# 18650_1S3P_Smart.net
KiCad netlist of a schematic drawn in EAGLE
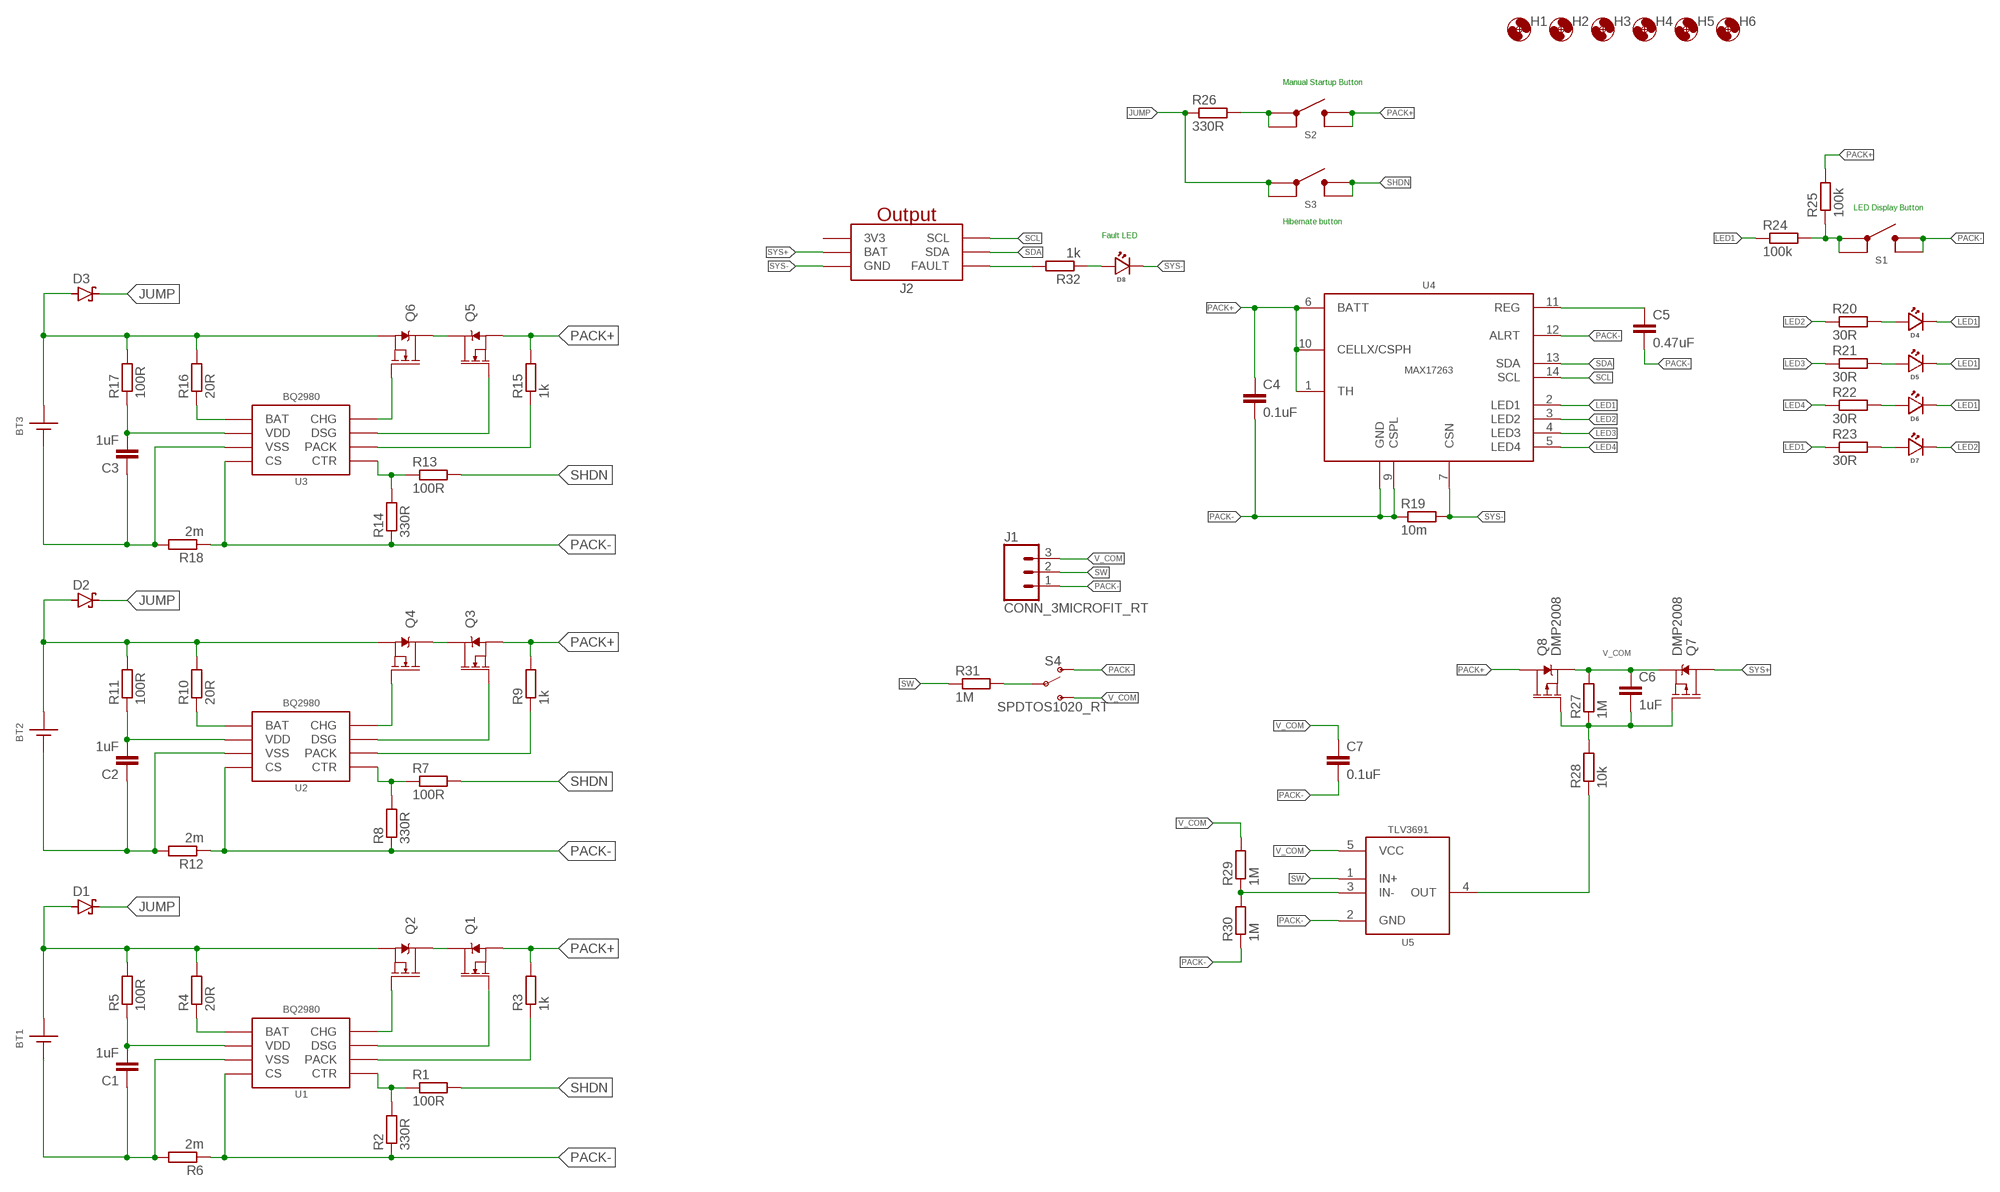
[diagram p0: schematic, sheet 1]

(export (version "E")
  (design (tool "Eeschema 10.0.6"))
  (components
    (comp (ref "BT1")
      (value "186501042P_NOSILK")
      (footprint "eagle-import:BATT_1042P_NOSILK")
      (fields (field (name "MF") "Keystone") (field (name "MPN") "1042P"))
      (libsource (lib "eagle-import") (part "186501042P_NOSILK"))
    )
    (comp (ref "BT2")
      (value "186501042P_NOSILK")
      (footprint "eagle-import:BATT_1042P_NOSILK")
      (fields (field (name "MF") "Keystone") (field (name "MPN") "1042P"))
      (libsource (lib "eagle-import") (part "186501042P_NOSILK"))
    )
    (comp (ref "BT3")
      (value "186501042P_NOSILK")
      (footprint "eagle-import:BATT_1042P_NOSILK")
      (fields (field (name "MF") "Keystone") (field (name "MPN") "1042P"))
      (libsource (lib "eagle-import") (part "186501042P_NOSILK"))
    )
    (comp (ref "C1")
      (value "1uF")
      (footprint "eagle-import:C0603")
      (fields (field (name "MF") "Yaiyo Yuden") (field (name "MPN") "EMK107BJ105KA-T"))
      (libsource (lib "eagle-import") (part "C-EUC06031UF"))
    )
    (comp (ref "C2")
      (value "1uF")
      (footprint "eagle-import:C0603")
      (fields (field (name "MF") "Yaiyo Yuden") (field (name "MPN") "EMK107BJ105KA-T"))
      (libsource (lib "eagle-import") (part "C-EUC06031UF"))
    )
    (comp (ref "C3")
      (value "1uF")
      (footprint "eagle-import:C0603")
      (fields (field (name "MF") "Yaiyo Yuden") (field (name "MPN") "EMK107BJ105KA-T"))
      (libsource (lib "eagle-import") (part "C-EUC06031UF"))
    )
    (comp (ref "C4")
      (value "0.1uF")
      (footprint "eagle-import:C0603")
      (fields (field (name "MF") "Murata") (field (name "MPN") "GCM188R71E104KA57D"))
      (libsource (lib "eagle-import") (part "C-EUC06030.1UF"))
    )
    (comp (ref "C5")
      (value "0.47uF")
      (footprint "eagle-import:C0603")
      (fields (field (name "MF") "Samsung") (field (name "MPN") "CL10B474KA8NNNC"))
      (libsource (lib "eagle-import") (part "C-EUC06030.47UF"))
    )
    (comp (ref "C6")
      (value "1uF")
      (footprint "eagle-import:C0603")
      (fields (field (name "MF") "Yaiyo Yuden") (field (name "MPN") "EMK107BJ105KA-T"))
      (libsource (lib "eagle-import") (part "C-EUC06031UF"))
    )
    (comp (ref "C7")
      (value "0.1uF")
      (footprint "eagle-import:C0603")
      (fields (field (name "MF") "Murata") (field (name "MPN") "GCM188R71E104KA57D"))
      (libsource (lib "eagle-import") (part "C-EUC06030.1UF"))
    )
    (comp (ref "D1")
      (value "DIODE_SCHOTTKYSOD-323")
      (footprint "eagle-import:SOD323-R")
      (fields
        (field (name "DIGIKEY") "BAT54WS-FDICT-ND")
        (field (name "MF") "Diodes Inc")
        (field (name "MPN") "BAT54WS-7-F")
      )
      (libsource (lib "eagle-import") (part "DIODE_SCHOTTKYSOD-323"))
    )
    (comp (ref "D2")
      (value "DIODE_SCHOTTKYSOD-323")
      (footprint "eagle-import:SOD323-R")
      (fields
        (field (name "DIGIKEY") "BAT54WS-FDICT-ND")
        (field (name "MF") "Diodes Inc")
        (field (name "MPN") "BAT54WS-7-F")
      )
      (libsource (lib "eagle-import") (part "DIODE_SCHOTTKYSOD-323"))
    )
    (comp (ref "D3")
      (value "DIODE_SCHOTTKYSOD-323")
      (footprint "eagle-import:SOD323-R")
      (fields
        (field (name "DIGIKEY") "BAT54WS-FDICT-ND")
        (field (name "MF") "Diodes Inc")
        (field (name "MPN") "BAT54WS-7-F")
      )
      (libsource (lib "eagle-import") (part "DIODE_SCHOTTKYSOD-323"))
    )
    (comp (ref "D4")
      (value "LED1206_BOTTOM")
      (footprint "eagle-import:LED_1206_BOTTOM")
      (fields (field (name "MF") "Lite-On") (field (name "MPN") "LTST-C230KGKT"))
      (libsource (lib "eagle-import") (part "LED1206_BOTTOM"))
    )
    (comp (ref "D5")
      (value "LED1206_BOTTOM")
      (footprint "eagle-import:LED_1206_BOTTOM")
      (fields (field (name "MF") "Lite-On") (field (name "MPN") "LTST-C230KGKT"))
      (libsource (lib "eagle-import") (part "LED1206_BOTTOM"))
    )
    (comp (ref "D6")
      (value "LED1206_BOTTOM")
      (footprint "eagle-import:LED_1206_BOTTOM")
      (fields (field (name "MF") "Lite-On") (field (name "MPN") "LTST-C230KGKT"))
      (libsource (lib "eagle-import") (part "LED1206_BOTTOM"))
    )
    (comp (ref "D7")
      (value "LED1206_BOTTOM")
      (footprint "eagle-import:LED_1206_BOTTOM")
      (fields (field (name "MF") "Lite-On") (field (name "MPN") "LTST-C230KGKT"))
      (libsource (lib "eagle-import") (part "LED1206_BOTTOM"))
    )
    (comp (ref "D8")
      (value "LED1206_BOTTOM")
      (footprint "eagle-import:LED_1206_BOTTOM")
      (fields (field (name "MF") "Lite-On") (field (name "MPN") "LTST-C230KRKT"))
      (libsource (lib "eagle-import") (part "LED1206_BOTTOM"))
    )
    (comp (ref "H1")
      (value "MOUNTING_HOLE4_NP")
      (footprint "eagle-import:4_40")
      (fields (field (name "MPN") "DNP"))
      (libsource (lib "eagle-import") (part "MOUNTING_HOLE4_NP"))
    )
    (comp (ref "H2")
      (value "MOUNTING_HOLE4_NP")
      (footprint "eagle-import:4_40")
      (fields (field (name "MPN") "DNP"))
      (libsource (lib "eagle-import") (part "MOUNTING_HOLE4_NP"))
    )
    (comp (ref "H3")
      (value "MOUNTING_HOLE4_NP")
      (footprint "eagle-import:4_40")
      (fields (field (name "MPN") "DNP"))
      (libsource (lib "eagle-import") (part "MOUNTING_HOLE4_NP"))
    )
    (comp (ref "H4")
      (value "MOUNTING_HOLE4_NP")
      (footprint "eagle-import:4_40")
      (fields (field (name "MPN") "DNP"))
      (libsource (lib "eagle-import") (part "MOUNTING_HOLE4_NP"))
    )
    (comp (ref "H5")
      (value "MOUNTING_HOLE4_NP")
      (footprint "eagle-import:4_40")
      (fields (field (name "MPN") "DNP"))
      (libsource (lib "eagle-import") (part "MOUNTING_HOLE4_NP"))
    )
    (comp (ref "H6")
      (value "MOUNTING_HOLE4_NP")
      (footprint "eagle-import:4_40")
      (fields (field (name "MPN") "DNP"))
      (libsource (lib "eagle-import") (part "MOUNTING_HOLE4_NP"))
    )
    (comp (ref "J1")
      (value "CONN_3MICROFIT_RT")
      (footprint "eagle-import:1X3_MICROFIT_RT")
      (fields (field (name "MF") "Molex") (field (name "MPN") "0436500300"))
      (libsource (lib "eagle-import") (part "CONN_3MICROFIT_RT"))
    )
    (comp (ref "J2")
      (value "GEMS_POWER_PLUGOUTPUT")
      (footprint "eagle-import:2X3_MICROFIT_RT")
      (fields (field (name "DISP") "Output") (field (name "MF") "Molex") (field (name "MPN") "0430450600"))
      (libsource (lib "eagle-import") (part "GEMS_POWER_PLUGOUTPUT"))
    )
    (comp (ref "Q1")
      (value "AON7522E")
      (footprint "eagle-import:DFN3X3A_8L_EP1_P")
      (fields (field (name "MF") "Alpha & Omega"))
      (libsource (lib "eagle-import") (part "MOSFET-NCH-AON7522E"))
    )
    (comp (ref "Q2")
      (value "AON7522E")
      (footprint "eagle-import:DFN3X3A_8L_EP1_P")
      (fields (field (name "MF") "Alpha & Omega"))
      (libsource (lib "eagle-import") (part "MOSFET-NCH-AON7522E"))
    )
    (comp (ref "Q3")
      (value "AON7522E")
      (footprint "eagle-import:DFN3X3A_8L_EP1_P")
      (fields (field (name "MF") "Alpha & Omega"))
      (libsource (lib "eagle-import") (part "MOSFET-NCH-AON7522E"))
    )
    (comp (ref "Q4")
      (value "AON7522E")
      (footprint "eagle-import:DFN3X3A_8L_EP1_P")
      (fields (field (name "MF") "Alpha & Omega"))
      (libsource (lib "eagle-import") (part "MOSFET-NCH-AON7522E"))
    )
    (comp (ref "Q5")
      (value "AON7522E")
      (footprint "eagle-import:DFN3X3A_8L_EP1_P")
      (fields (field (name "MF") "Alpha & Omega"))
      (libsource (lib "eagle-import") (part "MOSFET-NCH-AON7522E"))
    )
    (comp (ref "Q6")
      (value "AON7522E")
      (footprint "eagle-import:DFN3X3A_8L_EP1_P")
      (fields (field (name "MF") "Alpha & Omega"))
      (libsource (lib "eagle-import") (part "MOSFET-NCH-AON7522E"))
    )
    (comp (ref "Q7")
      (value "DMP2008")
      (footprint "eagle-import:POWERDI3333-8")
      (fields (field (name "MF") "Diodes Inc") (field (name "MPN") "DMP2008UFG-7"))
      (libsource (lib "eagle-import") (part "MOSFET-PCH-DMP2008"))
    )
    (comp (ref "Q8")
      (value "DMP2008")
      (footprint "eagle-import:POWERDI3333-8")
      (fields (field (name "MF") "Diodes Inc") (field (name "MPN") "DMP2008UFG-7"))
      (libsource (lib "eagle-import") (part "MOSFET-PCH-DMP2008"))
    )
    (comp (ref "R1")
      (value "100R")
      (footprint "eagle-import:R0603")
      (fields
        (field (name "MF") "Yageo")
        (field (name "MPN") "RC0603FR-07100RL")
        (field (name "VALUE_PART") "100")
      )
      (libsource (lib "eagle-import") (part "R-EU_R0603100"))
    )
    (comp (ref "R2")
      (value "330R")
      (footprint "eagle-import:R0603")
      (fields
        (field (name "MF") "Yageo")
        (field (name "MPN") "RC0603FR-07330RL")
        (field (name "VALUE_PART") "330")
      )
      (libsource (lib "eagle-import") (part "R-EU_R0603330"))
    )
    (comp (ref "R3")
      (value "1k")
      (footprint "eagle-import:R0603")
      (fields (field (name "MF") "Yageo") (field (name "MPN") "AC0603FR-071KL"))
      (libsource (lib "eagle-import") (part "R-EU_R06031K"))
    )
    (comp (ref "R4")
      (value "20R")
      (footprint "eagle-import:R0603")
      (fields
        (field (name "MF") "Yageo")
        (field (name "MPN") "RC0603FR-0720RL")
        (field (name "VALUE_PART") "20")
      )
      (libsource (lib "eagle-import") (part "R-EU_R060320"))
    )
    (comp (ref "R5")
      (value "100R")
      (footprint "eagle-import:R0603")
      (fields
        (field (name "MF") "Yageo")
        (field (name "MPN") "RC0603FR-07100RL")
        (field (name "VALUE_PART") "100")
      )
      (libsource (lib "eagle-import") (part "R-EU_R0603100"))
    )
    (comp (ref "R6")
      (value "2m")
      (footprint "eagle-import:R0805")
      (fields (field (name "MF") "Rohm") (field (name "MPN") "PMR10EZPFV2L00"))
      (libsource (lib "eagle-import") (part "R-EU_R08050.002"))
    )
    (comp (ref "R7")
      (value "100R")
      (footprint "eagle-import:R0603")
      (fields
        (field (name "MF") "Yageo")
        (field (name "MPN") "RC0603FR-07100RL")
        (field (name "VALUE_PART") "100")
      )
      (libsource (lib "eagle-import") (part "R-EU_R0603100"))
    )
    (comp (ref "R8")
      (value "330R")
      (footprint "eagle-import:R0603")
      (fields
        (field (name "MF") "Yageo")
        (field (name "MPN") "RC0603FR-07330RL")
        (field (name "VALUE_PART") "330")
      )
      (libsource (lib "eagle-import") (part "R-EU_R0603330"))
    )
    (comp (ref "R9")
      (value "1k")
      (footprint "eagle-import:R0603")
      (fields (field (name "MF") "Yageo") (field (name "MPN") "AC0603FR-071KL"))
      (libsource (lib "eagle-import") (part "R-EU_R06031K"))
    )
    (comp (ref "R10")
      (value "20R")
      (footprint "eagle-import:R0603")
      (fields
        (field (name "MF") "Yageo")
        (field (name "MPN") "RC0603FR-0720RL")
        (field (name "VALUE_PART") "20")
      )
      (libsource (lib "eagle-import") (part "R-EU_R060320"))
    )
    (comp (ref "R11")
      (value "100R")
      (footprint "eagle-import:R0603")
      (fields
        (field (name "MF") "Yageo")
        (field (name "MPN") "RC0603FR-07100RL")
        (field (name "VALUE_PART") "100")
      )
      (libsource (lib "eagle-import") (part "R-EU_R0603100"))
    )
    (comp (ref "R12")
      (value "2m")
      (footprint "eagle-import:R0805")
      (fields (field (name "MF") "Rohm") (field (name "MPN") "PMR10EZPFV2L00"))
      (libsource (lib "eagle-import") (part "R-EU_R08050.002"))
    )
    (comp (ref "R13")
      (value "100R")
      (footprint "eagle-import:R0603")
      (fields
        (field (name "MF") "Yageo")
        (field (name "MPN") "RC0603FR-07100RL")
        (field (name "VALUE_PART") "100")
      )
      (libsource (lib "eagle-import") (part "R-EU_R0603100"))
    )
    (comp (ref "R14")
      (value "330R")
      (footprint "eagle-import:R0603")
      (fields
        (field (name "MF") "Yageo")
        (field (name "MPN") "RC0603FR-07330RL")
        (field (name "VALUE_PART") "330")
      )
      (libsource (lib "eagle-import") (part "R-EU_R0603330"))
    )
    (comp (ref "R15")
      (value "1k")
      (footprint "eagle-import:R0603")
      (fields (field (name "MF") "Yageo") (field (name "MPN") "AC0603FR-071KL"))
      (libsource (lib "eagle-import") (part "R-EU_R06031K"))
    )
    (comp (ref "R16")
      (value "20R")
      (footprint "eagle-import:R0603")
      (fields
        (field (name "MF") "Yageo")
        (field (name "MPN") "RC0603FR-0720RL")
        (field (name "VALUE_PART") "20")
      )
      (libsource (lib "eagle-import") (part "R-EU_R060320"))
    )
    (comp (ref "R17")
      (value "100R")
      (footprint "eagle-import:R0603")
      (fields
        (field (name "MF") "Yageo")
        (field (name "MPN") "RC0603FR-07100RL")
        (field (name "VALUE_PART") "100")
      )
      (libsource (lib "eagle-import") (part "R-EU_R0603100"))
    )
    (comp (ref "R18")
      (value "2m")
      (footprint "eagle-import:R0805")
      (fields (field (name "MF") "Rohm") (field (name "MPN") "PMR10EZPFV2L00"))
      (libsource (lib "eagle-import") (part "R-EU_R08050.002"))
    )
    (comp (ref "R19")
      (value "10m")
      (footprint "eagle-import:R0805")
      (fields (field (name "MF") "Bourns") (field (name "MPN") "CRF0805-FZ-R010ELF"))
      (libsource (lib "eagle-import") (part "R-EU_R08050.01"))
    )
    (comp (ref "R20")
      (value "30R")
      (footprint "eagle-import:R0603")
      (fields
        (field (name "MF") "Yageo")
        (field (name "MPN") "RC0603FR-0730RL")
        (field (name "VALUE_PART") "30")
      )
      (libsource (lib "eagle-import") (part "R-EU_R060330"))
    )
    (comp (ref "R21")
      (value "30R")
      (footprint "eagle-import:R0603")
      (fields
        (field (name "MF") "Yageo")
        (field (name "MPN") "RC0603FR-0730RL")
        (field (name "VALUE_PART") "30")
      )
      (libsource (lib "eagle-import") (part "R-EU_R060330"))
    )
    (comp (ref "R22")
      (value "30R")
      (footprint "eagle-import:R0603")
      (fields
        (field (name "MF") "Yageo")
        (field (name "MPN") "RC0603FR-0730RL")
        (field (name "VALUE_PART") "30")
      )
      (libsource (lib "eagle-import") (part "R-EU_R060330"))
    )
    (comp (ref "R23")
      (value "30R")
      (footprint "eagle-import:R0603")
      (fields
        (field (name "MF") "Yageo")
        (field (name "MPN") "RC0603FR-0730RL")
        (field (name "VALUE_PART") "30")
      )
      (libsource (lib "eagle-import") (part "R-EU_R060330"))
    )
    (comp (ref "R24")
      (value "100k")
      (footprint "eagle-import:R0603")
      (fields (field (name "MF") "Yageo") (field (name "MPN") "RC0603FR-07100KL"))
      (libsource (lib "eagle-import") (part "R-EU_R0603100K"))
    )
    (comp (ref "R25")
      (value "100k")
      (footprint "eagle-import:R0603")
      (fields (field (name "MF") "Yageo") (field (name "MPN") "RC0603FR-07100KL"))
      (libsource (lib "eagle-import") (part "R-EU_R0603100K"))
    )
    (comp (ref "R26")
      (value "330R")
      (footprint "eagle-import:R0603")
      (fields
        (field (name "MF") "Yageo")
        (field (name "MPN") "RC0603FR-07330RL")
        (field (name "VALUE_PART") "330")
      )
      (libsource (lib "eagle-import") (part "R-EU_R0603330"))
    )
    (comp (ref "R27")
      (value "1M")
      (footprint "eagle-import:R0603")
      (fields (field (name "MF") "Panasonic") (field (name "MPN") "ERJ-3EKF1004V"))
      (libsource (lib "eagle-import") (part "R-EU_R06031M"))
    )
    (comp (ref "R28")
      (value "10k")
      (footprint "eagle-import:R0603")
      (fields (field (name "MF") "Yageo") (field (name "MPN") "RC0603FR-0710KL"))
      (libsource (lib "eagle-import") (part "R-EU_R060310K"))
    )
    (comp (ref "R29")
      (value "1M")
      (footprint "eagle-import:R0603")
      (fields (field (name "MF") "Panasonic") (field (name "MPN") "ERJ-3EKF1004V"))
      (libsource (lib "eagle-import") (part "R-EU_R06031M"))
    )
    (comp (ref "R30")
      (value "1M")
      (footprint "eagle-import:R0603")
      (fields (field (name "MF") "Panasonic") (field (name "MPN") "ERJ-3EKF1004V"))
      (libsource (lib "eagle-import") (part "R-EU_R06031M"))
    )
    (comp (ref "R31")
      (value "1M")
      (footprint "eagle-import:R0603")
      (fields (field (name "MF") "Panasonic") (field (name "MPN") "ERJ-3EKF1004V"))
      (libsource (lib "eagle-import") (part "R-EU_R06031M"))
    )
    (comp (ref "R32")
      (value "1k")
      (footprint "eagle-import:R0603")
      (fields (field (name "MF") "Yageo") (field (name "MPN") "AC0603FR-071KL"))
      (libsource (lib "eagle-import") (part "R-EU_R06031K"))
    )
    (comp (ref "S1")
      (value "BUTTON6X6_TH")
      (footprint "eagle-import:SWITCH_6MM_TH")
      (fields (field (name "MF") "TE Connectivity") (field (name "MPN") "1825910-6"))
      (libsource (lib "eagle-import") (part "BUTTON6X6_TH"))
    )
    (comp (ref "S2")
      (value "BUTTON6X6_TH")
      (footprint "eagle-import:SWITCH_6MM_TH")
      (fields (field (name "MF") "TE Connectivity") (field (name "MPN") "1825910-6"))
      (libsource (lib "eagle-import") (part "BUTTON6X6_TH"))
    )
    (comp (ref "S3")
      (value "BUTTON6X6_TH")
      (footprint "eagle-import:SWITCH_6MM_TH")
      (fields (field (name "MF") "TE Connectivity") (field (name "MPN") "1825910-6"))
      (libsource (lib "eagle-import") (part "BUTTON6X6_TH"))
    )
    (comp (ref "S4")
      (value "SPDTOS1020_RT")
      (footprint "eagle-import:OS102011MA1QN1")
      (fields (field (name "MF") "C&K") (field (name "MPN") "OS102011MA1QN1"))
      (libsource (lib "eagle-import") (part "SPDTOS1020_RT"))
    )
    (comp (ref "U1")
      (value "BQ2980RUG")
      (footprint "eagle-import:RUG_S-PQFP-N8")
      (fields (field (name "MF") "TI") (field (name "MPN") "BQ298000RUGT"))
      (libsource (lib "eagle-import") (part "BQ2980RUG"))
    )
    (comp (ref "U2")
      (value "BQ2980RUG")
      (footprint "eagle-import:RUG_S-PQFP-N8")
      (fields (field (name "MF") "TI") (field (name "MPN") "BQ298000RUGT"))
      (libsource (lib "eagle-import") (part "BQ2980RUG"))
    )
    (comp (ref "U3")
      (value "BQ2980RUG")
      (footprint "eagle-import:RUG_S-PQFP-N8")
      (fields (field (name "MF") "TI") (field (name "MPN") "BQ298000RUGT"))
      (libsource (lib "eagle-import") (part "BQ2980RUG"))
    )
    (comp (ref "U4")
      (value "MAX17263")
      (footprint "eagle-import:DFN_14_3X3")
      (fields (field (name "MF") "Maxim") (field (name "MPN") "MAX17263LETD+T"))
      (libsource (lib "eagle-import") (part "MAX17263"))
    )
    (comp (ref "U5")
      (value "TLV3691DCK")
      (footprint "eagle-import:DCK_R-PDSO-G5")
      (fields (field (name "MF") "TI") (field (name "MPN") "TLV3691IDCKR"))
      (libsource (lib "eagle-import") (part "TLV3691DCK"))
    )
  )
  (nets
    (net (code "1") (name "/3V3") (class "Default")
      (node (ref "J2") (pin "5") (pinfunction "3V3_5") (pintype "power_in"))
    )
    (net (code "2") (name "JUMP") (class "Default")
      (node (ref "D1") (pin "C") (pinfunction "C_C") (pintype "passive"))
      (node (ref "D2") (pin "C") (pinfunction "C_C") (pintype "passive"))
      (node (ref "D3") (pin "C") (pinfunction "C_C") (pintype "passive"))
      (node (ref "R26") (pin "1") (pinfunction "1_1") (pintype "passive"))
      (node (ref "S3") (pin "1") (pinfunction "1_1") (pintype "bidirectional"))
      (node (ref "S3") (pin "2") (pinfunction "2_2") (pintype "bidirectional"))
    )
    (net (code "3") (name "LED1") (class "Default")
      (node (ref "D4") (pin "CATHODE") (pinfunction "CATHODE_CATHODE") (pintype "power_in"))
      (node (ref "D5") (pin "CATHODE") (pinfunction "CATHODE_CATHODE") (pintype "power_in"))
      (node (ref "D6") (pin "CATHODE") (pinfunction "CATHODE_CATHODE") (pintype "power_in"))
      (node (ref "R23") (pin "1") (pinfunction "1_1") (pintype "passive"))
      (node (ref "R24") (pin "1") (pinfunction "1_1") (pintype "passive"))
      (node (ref "U4") (pin "2") (pinfunction "LED1_2") (pintype "bidirectional"))
    )
    (net (code "4") (name "LED2") (class "Default")
      (node (ref "D7") (pin "CATHODE") (pinfunction "CATHODE_CATHODE") (pintype "power_in"))
      (node (ref "R20") (pin "1") (pinfunction "1_1") (pintype "passive"))
      (node (ref "U4") (pin "3") (pinfunction "LED2_3") (pintype "bidirectional"))
    )
    (net (code "5") (name "LED3") (class "Default")
      (node (ref "R21") (pin "1") (pinfunction "1_1") (pintype "passive"))
      (node (ref "U4") (pin "4") (pinfunction "LED3_4") (pintype "bidirectional"))
    )
    (net (code "6") (name "LED4") (class "Default")
      (node (ref "R22") (pin "1") (pinfunction "1_1") (pintype "passive"))
      (node (ref "U4") (pin "5") (pinfunction "LED4_5") (pintype "bidirectional"))
    )
    (net (code "7") (name "Net-(BT1-+)") (class "Default")
      (node (ref "BT1") (pin "BATT+") (pinfunction "+_BATT+") (pintype "power_in"))
      (node (ref "D1") (pin "A") (pinfunction "A_A") (pintype "passive"))
      (node (ref "Q2") (pin "S@1") (pinfunction "S_S@1") (pintype "bidirectional"))
      (node (ref "Q2") (pin "S@2") (pinfunction "S_S@2") (pintype "bidirectional"))
      (node (ref "Q2") (pin "S@3") (pinfunction "S_S@3") (pintype "bidirectional"))
      (node (ref "R4") (pin "2") (pinfunction "2_2") (pintype "passive"))
      (node (ref "R5") (pin "2") (pinfunction "2_2") (pintype "passive"))
    )
    (net (code "8") (name "Net-(BT1--)") (class "Default")
      (node (ref "BT1") (pin "BATT-") (pinfunction "-_BATT-") (pintype "power_in"))
      (node (ref "C1") (pin "1") (pinfunction "1_1") (pintype "passive"))
      (node (ref "R6") (pin "2") (pinfunction "2_2") (pintype "passive"))
      (node (ref "U1") (pin "3") (pinfunction "VSS_3") (pintype "power_in"))
    )
    (net (code "9") (name "Net-(BT2-+)") (class "Default")
      (node (ref "BT2") (pin "BATT+") (pinfunction "+_BATT+") (pintype "power_in"))
      (node (ref "D2") (pin "A") (pinfunction "A_A") (pintype "passive"))
      (node (ref "Q4") (pin "S@1") (pinfunction "S_S@1") (pintype "bidirectional"))
      (node (ref "Q4") (pin "S@2") (pinfunction "S_S@2") (pintype "bidirectional"))
      (node (ref "Q4") (pin "S@3") (pinfunction "S_S@3") (pintype "bidirectional"))
      (node (ref "R10") (pin "2") (pinfunction "2_2") (pintype "passive"))
      (node (ref "R11") (pin "2") (pinfunction "2_2") (pintype "passive"))
    )
    (net (code "10") (name "Net-(BT2--)") (class "Default")
      (node (ref "BT2") (pin "BATT-") (pinfunction "-_BATT-") (pintype "power_in"))
      (node (ref "C2") (pin "1") (pinfunction "1_1") (pintype "passive"))
      (node (ref "R12") (pin "2") (pinfunction "2_2") (pintype "passive"))
      (node (ref "U2") (pin "3") (pinfunction "VSS_3") (pintype "power_in"))
    )
    (net (code "11") (name "Net-(BT3-+)") (class "Default")
      (node (ref "BT3") (pin "BATT+") (pinfunction "+_BATT+") (pintype "power_in"))
      (node (ref "D3") (pin "A") (pinfunction "A_A") (pintype "passive"))
      (node (ref "Q6") (pin "S@1") (pinfunction "S_S@1") (pintype "bidirectional"))
      (node (ref "Q6") (pin "S@2") (pinfunction "S_S@2") (pintype "bidirectional"))
      (node (ref "Q6") (pin "S@3") (pinfunction "S_S@3") (pintype "bidirectional"))
      (node (ref "R16") (pin "2") (pinfunction "2_2") (pintype "passive"))
      (node (ref "R17") (pin "2") (pinfunction "2_2") (pintype "passive"))
    )
    (net (code "12") (name "Net-(BT3--)") (class "Default")
      (node (ref "BT3") (pin "BATT-") (pinfunction "-_BATT-") (pintype "power_in"))
      (node (ref "C3") (pin "1") (pinfunction "1_1") (pintype "passive"))
      (node (ref "R18") (pin "2") (pinfunction "2_2") (pintype "passive"))
      (node (ref "U3") (pin "3") (pinfunction "VSS_3") (pintype "power_in"))
    )
    (net (code "13") (name "Net-(D4-PadANODE)") (class "Default")
      (node (ref "D4") (pin "ANODE") (pinfunction "ANODE_ANODE") (pintype "power_in"))
      (node (ref "R20") (pin "2") (pinfunction "2_2") (pintype "passive"))
    )
    (net (code "14") (name "Net-(D5-PadANODE)") (class "Default")
      (node (ref "D5") (pin "ANODE") (pinfunction "ANODE_ANODE") (pintype "power_in"))
      (node (ref "R21") (pin "2") (pinfunction "2_2") (pintype "passive"))
    )
    (net (code "15") (name "Net-(D6-PadANODE)") (class "Default")
      (node (ref "D6") (pin "ANODE") (pinfunction "ANODE_ANODE") (pintype "power_in"))
      (node (ref "R22") (pin "2") (pinfunction "2_2") (pintype "passive"))
    )
    (net (code "16") (name "Net-(D7-PadANODE)") (class "Default")
      (node (ref "D7") (pin "ANODE") (pinfunction "ANODE_ANODE") (pintype "power_in"))
      (node (ref "R23") (pin "2") (pinfunction "2_2") (pintype "passive"))
    )
    (net (code "17") (name "Net-(D8-PadANODE)") (class "Default")
      (node (ref "D8") (pin "ANODE") (pinfunction "ANODE_ANODE") (pintype "power_in"))
      (node (ref "R32") (pin "1") (pinfunction "1_1") (pintype "passive"))
    )
    (net (code "18") (name "Net-(J2-FAULT)") (class "Default")
      (node (ref "J2") (pin "1") (pinfunction "FAULT_1") (pintype "bidirectional"))
      (node (ref "R32") (pin "2") (pinfunction "2_2") (pintype "passive"))
    )
    (net (code "19") (name "Net-(Q1-PadD)") (class "Default")
      (node (ref "Q1") (pin "D") (pinfunction "D_D") (pintype "bidirectional"))
      (node (ref "Q2") (pin "D") (pinfunction "D_D") (pintype "bidirectional"))
    )
    (net (code "20") (name "Net-(Q3-PadD)") (class "Default")
      (node (ref "Q3") (pin "D") (pinfunction "D_D") (pintype "bidirectional"))
      (node (ref "Q4") (pin "D") (pinfunction "D_D") (pintype "bidirectional"))
    )
    (net (code "21") (name "Net-(Q5-PadD)") (class "Default")
      (node (ref "Q5") (pin "D") (pinfunction "D_D") (pintype "bidirectional"))
      (node (ref "Q6") (pin "D") (pinfunction "D_D") (pintype "bidirectional"))
    )
    (net (code "22") (name "Net-(Q7-G)") (class "Default")
      (node (ref "C6") (pin "2") (pinfunction "2_2") (pintype "passive"))
      (node (ref "Q7") (pin "4") (pinfunction "G_4") (pintype "bidirectional"))
      (node (ref "Q8") (pin "4") (pinfunction "G_4") (pintype "bidirectional"))
      (node (ref "R27") (pin "1") (pinfunction "1_1") (pintype "passive"))
      (node (ref "R28") (pin "2") (pinfunction "2_2") (pintype "passive"))
    )
    (net (code "23") (name "Net-(R24-Pad2)") (class "Default")
      (node (ref "R24") (pin "2") (pinfunction "2_2") (pintype "passive"))
      (node (ref "R25") (pin "1") (pinfunction "1_1") (pintype "passive"))
      (node (ref "S1") (pin "1") (pinfunction "1_1") (pintype "bidirectional"))
      (node (ref "S1") (pin "2") (pinfunction "2_2") (pintype "bidirectional"))
    )
    (net (code "24") (name "Net-(R26-Pad2)") (class "Default")
      (node (ref "R26") (pin "2") (pinfunction "2_2") (pintype "passive"))
      (node (ref "S2") (pin "1") (pinfunction "1_1") (pintype "bidirectional"))
      (node (ref "S2") (pin "2") (pinfunction "2_2") (pintype "bidirectional"))
    )
    (net (code "25") (name "Net-(S4-P)") (class "Default")
      (node (ref "R31") (pin "2") (pinfunction "2_2") (pintype "passive"))
      (node (ref "S4") (pin "2") (pinfunction "P_2") (pintype "passive"))
    )
    (net (code "26") (name "Net-(U1-BAT)") (class "Default")
      (node (ref "R4") (pin "1") (pinfunction "1_1") (pintype "passive"))
      (node (ref "U1") (pin "1") (pinfunction "BAT_1") (pintype "power_in"))
    )
    (net (code "27") (name "Net-(U1-CHG)") (class "Default")
      (node (ref "Q2") (pin "G") (pinfunction "G_G") (pintype "bidirectional"))
      (node (ref "U1") (pin "8") (pinfunction "CHG_8") (pintype "output"))
    )
    (net (code "28") (name "Net-(U1-CTR)") (class "Default")
      (node (ref "R1") (pin "1") (pinfunction "1_1") (pintype "passive"))
      (node (ref "R2") (pin "2") (pinfunction "2_2") (pintype "passive"))
      (node (ref "U1") (pin "5") (pinfunction "CTR_5") (pintype "input"))
    )
    (net (code "29") (name "Net-(U1-DSG)") (class "Default")
      (node (ref "Q1") (pin "G") (pinfunction "G_G") (pintype "bidirectional"))
      (node (ref "U1") (pin "7") (pinfunction "DSG_7") (pintype "output"))
    )
    (net (code "30") (name "Net-(U1-PACK)") (class "Default")
      (node (ref "R3") (pin "1") (pinfunction "1_1") (pintype "passive"))
      (node (ref "U1") (pin "6") (pinfunction "PACK_6") (pintype "input"))
    )
    (net (code "31") (name "Net-(U1-VDD)") (class "Default")
      (node (ref "C1") (pin "2") (pinfunction "2_2") (pintype "passive"))
      (node (ref "R5") (pin "1") (pinfunction "1_1") (pintype "passive"))
      (node (ref "U1") (pin "2") (pinfunction "VDD_2") (pintype "power_in"))
    )
    (net (code "32") (name "Net-(U2-BAT)") (class "Default")
      (node (ref "R10") (pin "1") (pinfunction "1_1") (pintype "passive"))
      (node (ref "U2") (pin "1") (pinfunction "BAT_1") (pintype "power_in"))
    )
    (net (code "33") (name "Net-(U2-CHG)") (class "Default")
      (node (ref "Q4") (pin "G") (pinfunction "G_G") (pintype "bidirectional"))
      (node (ref "U2") (pin "8") (pinfunction "CHG_8") (pintype "output"))
    )
    (net (code "34") (name "Net-(U2-CTR)") (class "Default")
      (node (ref "R7") (pin "1") (pinfunction "1_1") (pintype "passive"))
      (node (ref "R8") (pin "2") (pinfunction "2_2") (pintype "passive"))
      (node (ref "U2") (pin "5") (pinfunction "CTR_5") (pintype "input"))
    )
    (net (code "35") (name "Net-(U2-DSG)") (class "Default")
      (node (ref "Q3") (pin "G") (pinfunction "G_G") (pintype "bidirectional"))
      (node (ref "U2") (pin "7") (pinfunction "DSG_7") (pintype "output"))
    )
    (net (code "36") (name "Net-(U2-PACK)") (class "Default")
      (node (ref "R9") (pin "1") (pinfunction "1_1") (pintype "passive"))
      (node (ref "U2") (pin "6") (pinfunction "PACK_6") (pintype "input"))
    )
    (net (code "37") (name "Net-(U2-VDD)") (class "Default")
      (node (ref "C2") (pin "2") (pinfunction "2_2") (pintype "passive"))
      (node (ref "R11") (pin "1") (pinfunction "1_1") (pintype "passive"))
      (node (ref "U2") (pin "2") (pinfunction "VDD_2") (pintype "power_in"))
    )
    (net (code "38") (name "Net-(U3-BAT)") (class "Default")
      (node (ref "R16") (pin "1") (pinfunction "1_1") (pintype "passive"))
      (node (ref "U3") (pin "1") (pinfunction "BAT_1") (pintype "power_in"))
    )
    (net (code "39") (name "Net-(U3-CHG)") (class "Default")
      (node (ref "Q6") (pin "G") (pinfunction "G_G") (pintype "bidirectional"))
      (node (ref "U3") (pin "8") (pinfunction "CHG_8") (pintype "output"))
    )
    (net (code "40") (name "Net-(U3-CTR)") (class "Default")
      (node (ref "R13") (pin "1") (pinfunction "1_1") (pintype "passive"))
      (node (ref "R14") (pin "2") (pinfunction "2_2") (pintype "passive"))
      (node (ref "U3") (pin "5") (pinfunction "CTR_5") (pintype "input"))
    )
    (net (code "41") (name "Net-(U3-DSG)") (class "Default")
      (node (ref "Q5") (pin "G") (pinfunction "G_G") (pintype "bidirectional"))
      (node (ref "U3") (pin "7") (pinfunction "DSG_7") (pintype "output"))
    )
    (net (code "42") (name "Net-(U3-PACK)") (class "Default")
      (node (ref "R15") (pin "1") (pinfunction "1_1") (pintype "passive"))
      (node (ref "U3") (pin "6") (pinfunction "PACK_6") (pintype "input"))
    )
    (net (code "43") (name "Net-(U3-VDD)") (class "Default")
      (node (ref "C3") (pin "2") (pinfunction "2_2") (pintype "passive"))
      (node (ref "R17") (pin "1") (pinfunction "1_1") (pintype "passive"))
      (node (ref "U3") (pin "2") (pinfunction "VDD_2") (pintype "power_in"))
    )
    (net (code "44") (name "Net-(U4-REG)") (class "Default")
      (node (ref "C5") (pin "1") (pinfunction "1_1") (pintype "passive"))
      (node (ref "U4") (pin "11") (pinfunction "REG_11") (pintype "power_in"))
    )
    (net (code "45") (name "Net-(U5-IN-)") (class "Default")
      (node (ref "R29") (pin "1") (pinfunction "1_1") (pintype "passive"))
      (node (ref "R30") (pin "2") (pinfunction "2_2") (pintype "passive"))
      (node (ref "U5") (pin "3") (pinfunction "IN-_3") (pintype "input"))
    )
    (net (code "46") (name "Net-(U5-OUT)") (class "Default")
      (node (ref "R28") (pin "1") (pinfunction "1_1") (pintype "passive"))
      (node (ref "U5") (pin "4") (pinfunction "OUT_4") (pintype "output"))
    )
    (net (code "47") (name "PACK+") (class "Default")
      (node (ref "C4") (pin "1") (pinfunction "1_1") (pintype "passive"))
      (node (ref "Q1") (pin "S@1") (pinfunction "S_S@1") (pintype "bidirectional"))
      (node (ref "Q1") (pin "S@2") (pinfunction "S_S@2") (pintype "bidirectional"))
      (node (ref "Q1") (pin "S@3") (pinfunction "S_S@3") (pintype "bidirectional"))
      (node (ref "Q3") (pin "S@1") (pinfunction "S_S@1") (pintype "bidirectional"))
      (node (ref "Q3") (pin "S@2") (pinfunction "S_S@2") (pintype "bidirectional"))
      (node (ref "Q3") (pin "S@3") (pinfunction "S_S@3") (pintype "bidirectional"))
      (node (ref "Q5") (pin "S@1") (pinfunction "S_S@1") (pintype "bidirectional"))
      (node (ref "Q5") (pin "S@2") (pinfunction "S_S@2") (pintype "bidirectional"))
      (node (ref "Q5") (pin "S@3") (pinfunction "S_S@3") (pintype "bidirectional"))
      (node (ref "Q8") (pin "EP@1") (pinfunction "D_EP@1") (pintype "bidirectional"))
      (node (ref "Q8") (pin "EP@2") (pinfunction "D_EP@2") (pintype "bidirectional"))
      (node (ref "Q8") (pin "EP@3") (pinfunction "D_EP@3") (pintype "bidirectional"))
      (node (ref "Q8") (pin "EP@4") (pinfunction "D_EP@4") (pintype "bidirectional"))
      (node (ref "Q8") (pin "EP@5") (pinfunction "D_EP@5") (pintype "bidirectional"))
      (node (ref "R15") (pin "2") (pinfunction "2_2") (pintype "passive"))
      (node (ref "R25") (pin "2") (pinfunction "2_2") (pintype "passive"))
      (node (ref "R3") (pin "2") (pinfunction "2_2") (pintype "passive"))
      (node (ref "R9") (pin "2") (pinfunction "2_2") (pintype "passive"))
      (node (ref "S2") (pin "3") (pinfunction "3_3") (pintype "bidirectional"))
      (node (ref "S2") (pin "4") (pinfunction "4_4") (pintype "bidirectional"))
      (node (ref "U4") (pin "1") (pinfunction "TH_1") (pintype "input"))
      (node (ref "U4") (pin "10") (pinfunction "CELLX/CSPH_10") (pintype "input"))
      (node (ref "U4") (pin "6") (pinfunction "BATT_6") (pintype "power_in"))
    )
    (net (code "48") (name "PACK-") (class "Default")
      (node (ref "C4") (pin "2") (pinfunction "2_2") (pintype "passive"))
      (node (ref "C5") (pin "2") (pinfunction "2_2") (pintype "passive"))
      (node (ref "C7") (pin "2") (pinfunction "2_2") (pintype "passive"))
      (node (ref "J1") (pin "1") (pinfunction "1_1") (pintype "passive"))
      (node (ref "R12") (pin "1") (pinfunction "1_1") (pintype "passive"))
      (node (ref "R14") (pin "1") (pinfunction "1_1") (pintype "passive"))
      (node (ref "R18") (pin "1") (pinfunction "1_1") (pintype "passive"))
      (node (ref "R19") (pin "1") (pinfunction "1_1") (pintype "passive"))
      (node (ref "R2") (pin "1") (pinfunction "1_1") (pintype "passive"))
      (node (ref "R30") (pin "1") (pinfunction "1_1") (pintype "passive"))
      (node (ref "R6") (pin "1") (pinfunction "1_1") (pintype "passive"))
      (node (ref "R8") (pin "1") (pinfunction "1_1") (pintype "passive"))
      (node (ref "S1") (pin "3") (pinfunction "3_3") (pintype "bidirectional"))
      (node (ref "S1") (pin "4") (pinfunction "4_4") (pintype "bidirectional"))
      (node (ref "S4") (pin "1") (pinfunction "O_1") (pintype "passive"))
      (node (ref "U1") (pin "4") (pinfunction "CS_4") (pintype "input"))
      (node (ref "U2") (pin "4") (pinfunction "CS_4") (pintype "input"))
      (node (ref "U3") (pin "4") (pinfunction "CS_4") (pintype "input"))
      (node (ref "U4") (pin "12") (pinfunction "ALRT_12") (pintype "open_collector"))
      (node (ref "U4") (pin "8") (pinfunction "GND_8") (pintype "power_in"))
      (node (ref "U4") (pin "9") (pinfunction "CSPL_9") (pintype "input"))
      (node (ref "U4") (pin "EP") (pinfunction "GND_EP") (pintype "power_in"))
      (node (ref "U5") (pin "2") (pinfunction "GND_2") (pintype "power_in"))
    )
    (net (code "49") (name "SCL") (class "Default")
      (node (ref "J2") (pin "4") (pinfunction "SCL_4") (pintype "bidirectional"))
      (node (ref "U4") (pin "14") (pinfunction "SCL_14") (pintype "input"))
    )
    (net (code "50") (name "SDA") (class "Default")
      (node (ref "J2") (pin "6") (pinfunction "SDA_6") (pintype "bidirectional"))
      (node (ref "U4") (pin "13") (pinfunction "SDA_13") (pintype "bidirectional"))
    )
    (net (code "51") (name "SHDN") (class "Default")
      (node (ref "R1") (pin "2") (pinfunction "2_2") (pintype "passive"))
      (node (ref "R13") (pin "2") (pinfunction "2_2") (pintype "passive"))
      (node (ref "R7") (pin "2") (pinfunction "2_2") (pintype "passive"))
      (node (ref "S3") (pin "3") (pinfunction "3_3") (pintype "bidirectional"))
      (node (ref "S3") (pin "4") (pinfunction "4_4") (pintype "bidirectional"))
    )
    (net (code "52") (name "SW") (class "Default")
      (node (ref "J1") (pin "2") (pinfunction "2_2") (pintype "passive"))
      (node (ref "R31") (pin "1") (pinfunction "1_1") (pintype "passive"))
      (node (ref "U5") (pin "1") (pinfunction "IN+_1") (pintype "input"))
    )
    (net (code "53") (name "SYS+") (class "Default")
      (node (ref "J2") (pin "3") (pinfunction "BAT_3") (pintype "power_in"))
      (node (ref "Q7") (pin "EP@1") (pinfunction "D_EP@1") (pintype "bidirectional"))
      (node (ref "Q7") (pin "EP@2") (pinfunction "D_EP@2") (pintype "bidirectional"))
      (node (ref "Q7") (pin "EP@3") (pinfunction "D_EP@3") (pintype "bidirectional"))
      (node (ref "Q7") (pin "EP@4") (pinfunction "D_EP@4") (pintype "bidirectional"))
      (node (ref "Q7") (pin "EP@5") (pinfunction "D_EP@5") (pintype "bidirectional"))
    )
    (net (code "54") (name "SYS-") (class "Default")
      (node (ref "D8") (pin "CATHODE") (pinfunction "CATHODE_CATHODE") (pintype "power_in"))
      (node (ref "J2") (pin "2") (pinfunction "GND_2") (pintype "power_in"))
      (node (ref "R19") (pin "2") (pinfunction "2_2") (pintype "passive"))
      (node (ref "U4") (pin "7") (pinfunction "CSN_7") (pintype "input"))
    )
    (net (code "55") (name "V_COM") (class "Default")
      (node (ref "C6") (pin "1") (pinfunction "1_1") (pintype "passive"))
      (node (ref "C7") (pin "1") (pinfunction "1_1") (pintype "passive"))
      (node (ref "J1") (pin "3") (pinfunction "3_3") (pintype "passive"))
      (node (ref "Q7") (pin "1") (pinfunction "S_1") (pintype "bidirectional"))
      (node (ref "Q7") (pin "2") (pinfunction "S_2") (pintype "bidirectional"))
      (node (ref "Q7") (pin "3") (pinfunction "S_3") (pintype "bidirectional"))
      (node (ref "Q8") (pin "1") (pinfunction "S_1") (pintype "bidirectional"))
      (node (ref "Q8") (pin "2") (pinfunction "S_2") (pintype "bidirectional"))
      (node (ref "Q8") (pin "3") (pinfunction "S_3") (pintype "bidirectional"))
      (node (ref "R27") (pin "2") (pinfunction "2_2") (pintype "passive"))
      (node (ref "R29") (pin "2") (pinfunction "2_2") (pintype "passive"))
      (node (ref "S4") (pin "3") (pinfunction "S_3") (pintype "passive"))
      (node (ref "U5") (pin "5") (pinfunction "VCC_5") (pintype "power_in"))
    )
  )
)
